# altium.net
KiCad netlist of a schematic drawn in Altium Designer
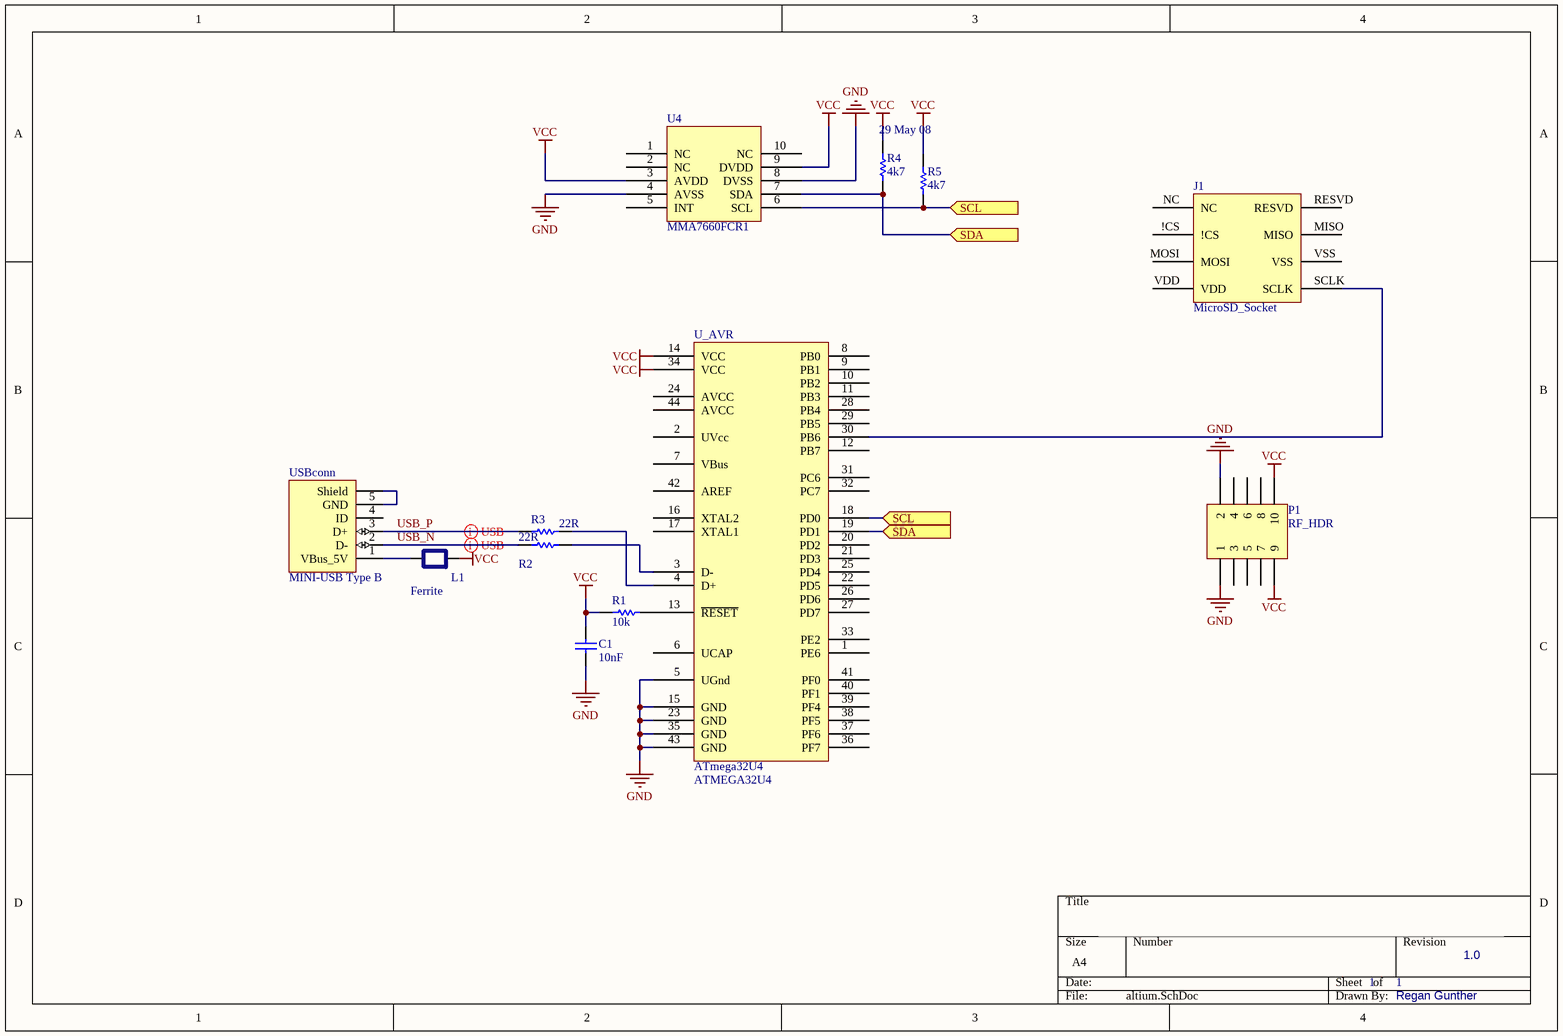
[diagram p0: altium.SchDoc]

(export (version "E")
  (design (tool "Eeschema 10.0.6"))
  (components
    (comp (ref "C1")
      (value "10nF")
      (footprint "SFE-Custom-Footprints:0603")
      (description "CAP CER 10000PF 100V X7R 0603")
      (fields (field (name "MANUFACTURER") "Taiyo Yuden"))
      (libsource (lib "ENEL429_2") (part "CP_10nF 0603"))
    )
    (comp (ref "J1")
      (value "MicroSD_Socket")
      (footprint "MicroSD")
      (libsource (lib "Atmega32U2") (part "MicroSD_Socket"))
    )
    (comp (ref "L1")
      (value "Ferrite")
      (footprint "0805")
      (description "FERRITE CHIP 120 OHM 800mA 0805")
      (fields (field (name "MANUFACTURER") "TDK"))
      (libsource (lib "ENEL429_2") (part "IN_FERRITE CHIP 120 OHM 800mA 0805"))
    )
    (comp (ref "P1")
      (value "RF_HDR")
      (footprint "Header SMD 2x10 Female")
      (description "Header, 5-Pin, Dual row")
      (fields (field (name "PUBLISHER") "Altium Limited"))
      (libsource (lib "Miscellaneous Connectors") (part "Header 5X2"))
    )
    (comp (ref "R1")
      (value "10k")
      (footprint "0603")
      (description "RES 10.0K OHM 1/10W 1% 0603 SMD")
      (fields (field (name "MANUFACTURER") "Yageo"))
      (libsource (lib "ENEL429_2") (part "RS_10k 0603"))
    )
    (comp (ref "R2")
      (value "22R")
      (footprint "0603")
      (description "RES 22 OHM 1/10W 1% 0603 SMD")
      (fields (field (name "MANUFACTURER") "Yageo"))
      (libsource (lib "ENEL429_2") (part "RS_22R 0603"))
    )
    (comp (ref "R3")
      (value "22R")
      (footprint "0603")
      (description "RES 22 OHM 1/10W 1% 0603 SMD")
      (fields (field (name "MANUFACTURER") "Yageo"))
      (libsource (lib "ENEL429_2") (part "RS_22R 0603"))
    )
    (comp (ref "R4")
      (value "4k7")
      (footprint "0603")
      (description "RES 4.70K OHM 1/10W 1% 0603 SMD")
      (fields (field (name "LATESTREVISIONDATE") "29 May 08") (field (name "MANUFACTURER") "ROHM"))
      (libsource (lib "ENEL429_2") (part "RS_4k7 0603"))
    )
    (comp (ref "R5")
      (value "4k7")
      (footprint "0603")
      (description "RES 4.70K OHM 1/10W 1% 0603 SMD")
      (fields (field (name "MANUFACTURER") "ROHM"))
      (libsource (lib "ENEL429_2") (part "RS_4k7 0603"))
    )
    (comp (ref "U4")
      (value "MMA7660FCR1")
      (footprint "DFN-10__MMA7660FCR1")
      (libsource (lib "FreescaleMMA7660FCR1") (part "MMA7660FCR1"))
    )
    (comp (ref "USBconn")
      (value "MINI-USB Type B")
      (footprint "USB-B SMD")
      (description "MINI-USB Type B Single Connector")
      (fields (field (name "MANUFACTURER") "Hirose Electric Co Ltd"))
      (libsource (lib "ENEL429_2") (part "JP_MINIUSB type B_1"))
    )
    (comp (ref "U_AVR")
      (value "ATmega32U4")
      (footprint "TQFP-44")
      (description "AVR 8-bit USB microcontroller")
      (fields (field (name "SUPPLIER PART NUMBER 1") "ATMEGA32U4"))
      (libsource (lib "ENEL429_2") (part "IC_ATmega32U4_44-TQFP"))
    )
  )
  (nets
    (net (code "1") (name "/SCL") (class "Default")
      (node (ref "R5") (pin "1") (pinfunction "1_1") (pintype "passive"))
      (node (ref "U4") (pin "6") (pinfunction "SCL_6") (pintype "passive"))
      (node (ref "U_AVR") (pin "18") (pinfunction "PD0_18") (pintype "passive"))
    )
    (net (code "2") (name "/SDA") (class "Default")
      (node (ref "R4") (pin "1") (pinfunction "1_1") (pintype "passive"))
      (node (ref "U4") (pin "7") (pinfunction "SDA_7") (pintype "passive"))
      (node (ref "U_AVR") (pin "19") (pinfunction "PD1_19") (pintype "passive"))
    )
    (net (code "3") (name "/USB_N") (class "Default")
      (node (ref "R2") (pin "1") (pinfunction "1_1") (pintype "passive"))
      (node (ref "USBconn") (pin "2") (pinfunction "D-_2") (pintype "bidirectional"))
    )
    (net (code "4") (name "/USB_P") (class "Default")
      (node (ref "R3") (pin "1") (pinfunction "1_1") (pintype "passive"))
      (node (ref "USBconn") (pin "3") (pinfunction "D+_3") (pintype "bidirectional"))
    )
    (net (code "5") (name "GND") (class "Default")
      (node (ref "C1") (pin "2") (pinfunction "2_2") (pintype "passive"))
      (node (ref "P1") (pin "1") (pinfunction "1_1") (pintype "passive"))
      (node (ref "P1") (pin "2") (pinfunction "2_2") (pintype "passive"))
      (node (ref "U4") (pin "4") (pinfunction "AVSS_4") (pintype "passive"))
      (node (ref "U4") (pin "8") (pinfunction "DVSS_8") (pintype "passive"))
      (node (ref "U_AVR") (pin "15") (pinfunction "GND_15") (pintype "power_in"))
      (node (ref "U_AVR") (pin "23") (pinfunction "GND_23") (pintype "power_in"))
      (node (ref "U_AVR") (pin "35") (pinfunction "GND_35") (pintype "passive"))
      (node (ref "U_AVR") (pin "43") (pinfunction "GND_43") (pintype "power_in"))
      (node (ref "U_AVR") (pin "5") (pinfunction "UGnd_5") (pintype "passive"))
    )
    (net (code "6") (name "Net-(L1-0)") (class "Default")
      (node (ref "L1") (pin "1") (pinfunction "0_1") (pintype "power_in"))
      (node (ref "USBconn") (pin "1") (pinfunction "VBus_5V_1") (pintype "passive"))
    )
    (net (code "7") (name "Net-(USBconn-GND)") (class "Default")
      (node (ref "USBconn") (pin "5") (pinfunction "GND_5") (pintype "passive"))
      (node (ref "USBconn") (pin "6") (pinfunction "Shield_6") (pintype "passive"))
    )
    (net (code "8") (name "Net-(U_AVR-D+)") (class "Default")
      (node (ref "R3") (pin "2") (pinfunction "2_2") (pintype "passive"))
      (node (ref "U_AVR") (pin "4") (pinfunction "D+_4") (pintype "passive"))
    )
    (net (code "9") (name "Net-(U_AVR-D-)") (class "Default")
      (node (ref "R2") (pin "2") (pinfunction "2_2") (pintype "passive"))
      (node (ref "U_AVR") (pin "3") (pinfunction "D-_3") (pintype "passive"))
    )
    (net (code "10") (name "Net-(U_AVR-PB6)") (class "Default")
      (node (ref "J1") (pin "SCLK") (pinfunction "SCLK_SCLK") (pintype "passive"))
      (node (ref "U_AVR") (pin "30") (pinfunction "PB6_30") (pintype "passive"))
    )
    (net (code "11") (name "Net-(U_AVR-~{RESET})") (class "Default")
      (node (ref "R1") (pin "1") (pinfunction "1_1") (pintype "passive"))
      (node (ref "U_AVR") (pin "13") (pinfunction "~{RESET}_13") (pintype "passive"))
    )
    (net (code "12") (name "VCC") (class "Default")
      (node (ref "C1") (pin "1") (pinfunction "1_1") (pintype "passive"))
      (node (ref "L1") (pin "2") (pinfunction "1_2") (pintype "power_in"))
      (node (ref "P1") (pin "10") (pinfunction "10_10") (pintype "passive"))
      (node (ref "P1") (pin "9") (pinfunction "9_9") (pintype "passive"))
      (node (ref "R1") (pin "2") (pinfunction "2_2") (pintype "passive"))
      (node (ref "R4") (pin "2") (pinfunction "2_2") (pintype "passive"))
      (node (ref "R5") (pin "2") (pinfunction "2_2") (pintype "passive"))
      (node (ref "U4") (pin "3") (pinfunction "AVDD_3") (pintype "passive"))
      (node (ref "U4") (pin "9") (pinfunction "DVDD_9") (pintype "passive"))
      (node (ref "U_AVR") (pin "14") (pinfunction "VCC_14") (pintype "power_in"))
      (node (ref "U_AVR") (pin "34") (pinfunction "VCC_34") (pintype "power_in"))
    )
    (net (code "13") (name "unconnected-(J1-Pad!CS)") (class "Default")
      (node (ref "J1") (pin "!CS") (pinfunction "!CS_!CS") (pintype "passive"))
    )
    (net (code "14") (name "unconnected-(J1-PadMISO)") (class "Default")
      (node (ref "J1") (pin "MISO") (pinfunction "MISO_MISO") (pintype "passive"))
    )
    (net (code "15") (name "unconnected-(J1-PadMOSI)") (class "Default")
      (node (ref "J1") (pin "MOSI") (pinfunction "MOSI_MOSI") (pintype "passive"))
    )
    (net (code "16") (name "unconnected-(J1-PadNC)") (class "Default")
      (node (ref "J1") (pin "NC") (pinfunction "NC_NC") (pintype "passive"))
    )
    (net (code "17") (name "unconnected-(J1-PadRESVD)") (class "Default")
      (node (ref "J1") (pin "RESVD") (pinfunction "RESVD_RESVD") (pintype "passive"))
    )
    (net (code "18") (name "unconnected-(J1-PadVDD)") (class "Default")
      (node (ref "J1") (pin "VDD") (pinfunction "VDD_VDD") (pintype "passive"))
    )
    (net (code "19") (name "unconnected-(J1-PadVSS)") (class "Default")
      (node (ref "J1") (pin "VSS") (pinfunction "VSS_VSS") (pintype "passive"))
    )
    (net (code "20") (name "unconnected-(P1-Pad3)") (class "Default")
      (node (ref "P1") (pin "3") (pinfunction "3_3") (pintype "passive"))
    )
    (net (code "21") (name "unconnected-(P1-Pad4)") (class "Default")
      (node (ref "P1") (pin "4") (pinfunction "4_4") (pintype "passive"))
    )
    (net (code "22") (name "unconnected-(P1-Pad5)") (class "Default")
      (node (ref "P1") (pin "5") (pinfunction "5_5") (pintype "passive"))
    )
    (net (code "23") (name "unconnected-(P1-Pad6)") (class "Default")
      (node (ref "P1") (pin "6") (pinfunction "6_6") (pintype "passive"))
    )
    (net (code "24") (name "unconnected-(P1-Pad7)") (class "Default")
      (node (ref "P1") (pin "7") (pinfunction "7_7") (pintype "passive"))
    )
    (net (code "25") (name "unconnected-(P1-Pad8)") (class "Default")
      (node (ref "P1") (pin "8") (pinfunction "8_8") (pintype "passive"))
    )
    (net (code "26") (name "unconnected-(U4-INT-Pad5)") (class "Default")
      (node (ref "U4") (pin "5") (pinfunction "INT_5") (pintype "passive"))
    )
    (net (code "27") (name "unconnected-(U4-NC-Pad1)") (class "Default")
      (node (ref "U4") (pin "1") (pinfunction "NC_1") (pintype "passive"))
    )
    (net (code "28") (name "unconnected-(U4-NC-Pad2)") (class "Default")
      (node (ref "U4") (pin "2") (pinfunction "NC_2") (pintype "passive"))
    )
    (net (code "29") (name "unconnected-(U4-NC-Pad10)") (class "Default")
      (node (ref "U4") (pin "10") (pinfunction "NC_10") (pintype "passive"))
    )
    (net (code "30") (name "unconnected-(USBconn-ID-Pad4)") (class "Default")
      (node (ref "USBconn") (pin "4") (pinfunction "ID_4") (pintype "passive"))
    )
    (net (code "31") (name "unconnected-(U_AVR-AREF-Pad42)") (class "Default")
      (node (ref "U_AVR") (pin "42") (pinfunction "AREF_42") (pintype "power_in"))
    )
    (net (code "32") (name "unconnected-(U_AVR-AVCC-Pad24)") (class "Default")
      (node (ref "U_AVR") (pin "24") (pinfunction "AVCC_24") (pintype "passive"))
    )
    (net (code "33") (name "unconnected-(U_AVR-AVCC-Pad44)") (class "Default")
      (node (ref "U_AVR") (pin "44") (pinfunction "AVCC_44") (pintype "power_in"))
    )
    (net (code "34") (name "unconnected-(U_AVR-PB0-Pad8)") (class "Default")
      (node (ref "U_AVR") (pin "8") (pinfunction "PB0_8") (pintype "passive"))
    )
    (net (code "35") (name "unconnected-(U_AVR-PB1-Pad9)") (class "Default")
      (node (ref "U_AVR") (pin "9") (pinfunction "PB1_9") (pintype "passive"))
    )
    (net (code "36") (name "unconnected-(U_AVR-PB2-Pad10)") (class "Default")
      (node (ref "U_AVR") (pin "10") (pinfunction "PB2_10") (pintype "passive"))
    )
    (net (code "37") (name "unconnected-(U_AVR-PB3-Pad11)") (class "Default")
      (node (ref "U_AVR") (pin "11") (pinfunction "PB3_11") (pintype "passive"))
    )
    (net (code "38") (name "unconnected-(U_AVR-PB4-Pad28)") (class "Default")
      (node (ref "U_AVR") (pin "28") (pinfunction "PB4_28") (pintype "passive"))
    )
    (net (code "39") (name "unconnected-(U_AVR-PB5-Pad29)") (class "Default")
      (node (ref "U_AVR") (pin "29") (pinfunction "PB5_29") (pintype "passive"))
    )
    (net (code "40") (name "unconnected-(U_AVR-PB7-Pad12)") (class "Default")
      (node (ref "U_AVR") (pin "12") (pinfunction "PB7_12") (pintype "power_in"))
    )
    (net (code "41") (name "unconnected-(U_AVR-PC6-Pad31)") (class "Default")
      (node (ref "U_AVR") (pin "31") (pinfunction "PC6_31") (pintype "passive"))
    )
    (net (code "42") (name "unconnected-(U_AVR-PC7-Pad32)") (class "Default")
      (node (ref "U_AVR") (pin "32") (pinfunction "PC7_32") (pintype "passive"))
    )
    (net (code "43") (name "unconnected-(U_AVR-PD2-Pad20)") (class "Default")
      (node (ref "U_AVR") (pin "20") (pinfunction "PD2_20") (pintype "passive"))
    )
    (net (code "44") (name "unconnected-(U_AVR-PD3-Pad21)") (class "Default")
      (node (ref "U_AVR") (pin "21") (pinfunction "PD3_21") (pintype "passive"))
    )
    (net (code "45") (name "unconnected-(U_AVR-PD4-Pad25)") (class "Default")
      (node (ref "U_AVR") (pin "25") (pinfunction "PD4_25") (pintype "passive"))
    )
    (net (code "46") (name "unconnected-(U_AVR-PD5-Pad22)") (class "Default")
      (node (ref "U_AVR") (pin "22") (pinfunction "PD5_22") (pintype "passive"))
    )
    (net (code "47") (name "unconnected-(U_AVR-PD6-Pad26)") (class "Default")
      (node (ref "U_AVR") (pin "26") (pinfunction "PD6_26") (pintype "passive"))
    )
    (net (code "48") (name "unconnected-(U_AVR-PD7-Pad27)") (class "Default")
      (node (ref "U_AVR") (pin "27") (pinfunction "PD7_27") (pintype "passive"))
    )
    (net (code "49") (name "unconnected-(U_AVR-PE2-Pad33)") (class "Default")
      (node (ref "U_AVR") (pin "33") (pinfunction "PE2_33") (pintype "passive"))
    )
    (net (code "50") (name "unconnected-(U_AVR-PE6-Pad1)") (class "Default")
      (node (ref "U_AVR") (pin "1") (pinfunction "PE6_1") (pintype "power_in"))
    )
    (net (code "51") (name "unconnected-(U_AVR-PF0-Pad41)") (class "Default")
      (node (ref "U_AVR") (pin "41") (pinfunction "PF0_41") (pintype "passive"))
    )
    (net (code "52") (name "unconnected-(U_AVR-PF1-Pad40)") (class "Default")
      (node (ref "U_AVR") (pin "40") (pinfunction "PF1_40") (pintype "power_in"))
    )
    (net (code "53") (name "unconnected-(U_AVR-PF4-Pad39)") (class "Default")
      (node (ref "U_AVR") (pin "39") (pinfunction "PF4_39") (pintype "power_in"))
    )
    (net (code "54") (name "unconnected-(U_AVR-PF5-Pad38)") (class "Default")
      (node (ref "U_AVR") (pin "38") (pinfunction "PF5_38") (pintype "power_in"))
    )
    (net (code "55") (name "unconnected-(U_AVR-PF6-Pad37)") (class "Default")
      (node (ref "U_AVR") (pin "37") (pinfunction "PF6_37") (pintype "power_in"))
    )
    (net (code "56") (name "unconnected-(U_AVR-PF7-Pad36)") (class "Default")
      (node (ref "U_AVR") (pin "36") (pinfunction "PF7_36") (pintype "power_in"))
    )
    (net (code "57") (name "unconnected-(U_AVR-UCAP-Pad6)") (class "Default")
      (node (ref "U_AVR") (pin "6") (pinfunction "UCAP_6") (pintype "passive"))
    )
    (net (code "58") (name "unconnected-(U_AVR-UVcc-Pad2)") (class "Default")
      (node (ref "U_AVR") (pin "2") (pinfunction "UVcc_2") (pintype "power_in"))
    )
    (net (code "59") (name "unconnected-(U_AVR-VBus-Pad7)") (class "Default")
      (node (ref "U_AVR") (pin "7") (pinfunction "VBus_7") (pintype "power_in"))
    )
    (net (code "60") (name "unconnected-(U_AVR-XTAL1-Pad17)") (class "Default")
      (node (ref "U_AVR") (pin "17") (pinfunction "XTAL1_17") (pintype "passive"))
    )
    (net (code "61") (name "unconnected-(U_AVR-XTAL2-Pad16)") (class "Default")
      (node (ref "U_AVR") (pin "16") (pinfunction "XTAL2_16") (pintype "passive"))
    )
  )
)
